# Cell_Balancing.net
KiCad netlist of a schematic drawn in Altium Designer
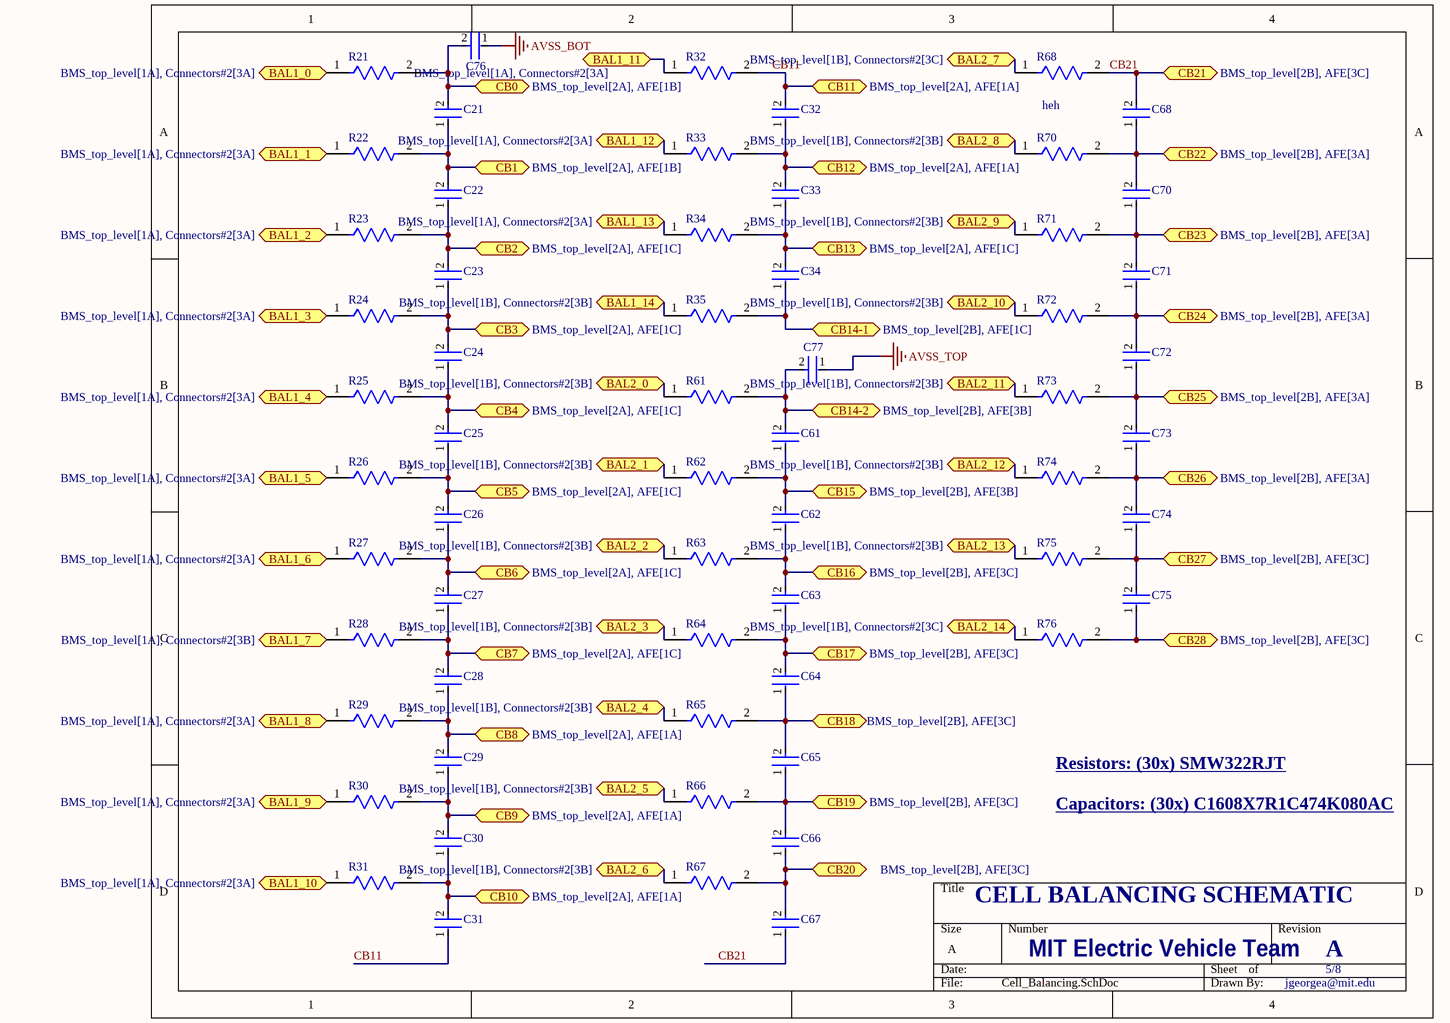
[diagram p0: Cell_Balancing.SchDoc]

(export (version "E")
  (design (tool "Eeschema 10.0.6"))
  (components
    (comp (ref "C21")
      (value "C1608X7R1C474K080AC")
      (footprint "FP-C1608-080-0_1-IPC_C")
      (description "Multilayer Ceramic Capacitors 470nF ±10% 16V X7R SMD 0603")
      (fields (field (name "VOLTAGE") "16V") (field (name "TOLERANCE") "10%"))
      (libsource (lib "Altium Content Vault") (part "236180d848d6139a670b325ea6854c9"))
    )
    (comp (ref "C22")
      (value "C1608X7R1C474K080AC")
      (footprint "FP-C1608-080-0_1-IPC_C")
      (description "Multilayer Ceramic Capacitors 470nF ±10% 16V X7R SMD 0603")
      (fields (field (name "VOLTAGE") "16V") (field (name "TOLERANCE") "10%"))
      (libsource (lib "Altium Content Vault") (part "236180d848d6139a670b325ea6854c9"))
    )
    (comp (ref "C23")
      (value "C1608X7R1C474K080AC")
      (footprint "FP-C1608-080-0_1-IPC_C")
      (description "Multilayer Ceramic Capacitors 470nF ±10% 16V X7R SMD 0603")
      (fields (field (name "VOLTAGE") "16V") (field (name "TOLERANCE") "10%"))
      (libsource (lib "Altium Content Vault") (part "236180d848d6139a670b325ea6854c9"))
    )
    (comp (ref "C24")
      (value "C1608X7R1C474K080AC")
      (footprint "FP-C1608-080-0_1-IPC_C")
      (description "Multilayer Ceramic Capacitors 470nF ±10% 16V X7R SMD 0603")
      (fields (field (name "VOLTAGE") "16V") (field (name "TOLERANCE") "10%"))
      (libsource (lib "Altium Content Vault") (part "236180d848d6139a670b325ea6854c9"))
    )
    (comp (ref "C25")
      (value "C1608X7R1C474K080AC")
      (footprint "FP-C1608-080-0_1-IPC_C")
      (description "Multilayer Ceramic Capacitors 470nF ±10% 16V X7R SMD 0603")
      (fields (field (name "VOLTAGE") "16V") (field (name "TOLERANCE") "10%"))
      (libsource (lib "Altium Content Vault") (part "236180d848d6139a670b325ea6854c9"))
    )
    (comp (ref "C26")
      (value "C1608X7R1C474K080AC")
      (footprint "FP-C1608-080-0_1-IPC_C")
      (description "Multilayer Ceramic Capacitors 470nF ±10% 16V X7R SMD 0603")
      (fields (field (name "VOLTAGE") "16V") (field (name "TOLERANCE") "10%"))
      (libsource (lib "Altium Content Vault") (part "236180d848d6139a670b325ea6854c9"))
    )
    (comp (ref "C27")
      (value "C1608X7R1C474K080AC")
      (footprint "FP-C1608-080-0_1-IPC_C")
      (description "Multilayer Ceramic Capacitors 470nF ±10% 16V X7R SMD 0603")
      (fields (field (name "VOLTAGE") "16V") (field (name "TOLERANCE") "10%"))
      (libsource (lib "Altium Content Vault") (part "236180d848d6139a670b325ea6854c9"))
    )
    (comp (ref "C28")
      (value "C1608X7R1C474K080AC")
      (footprint "FP-C1608-080-0_1-IPC_C")
      (description "Multilayer Ceramic Capacitors 470nF ±10% 16V X7R SMD 0603")
      (fields (field (name "VOLTAGE") "16V") (field (name "TOLERANCE") "10%"))
      (libsource (lib "Altium Content Vault") (part "236180d848d6139a670b325ea6854c9"))
    )
    (comp (ref "C29")
      (value "C1608X7R1C474K080AC")
      (footprint "FP-C1608-080-0_1-IPC_C")
      (description "Multilayer Ceramic Capacitors 470nF ±10% 16V X7R SMD 0603")
      (fields (field (name "VOLTAGE") "16V") (field (name "TOLERANCE") "10%"))
      (libsource (lib "Altium Content Vault") (part "236180d848d6139a670b325ea6854c9"))
    )
    (comp (ref "C30")
      (value "C1608X7R1C474K080AC")
      (footprint "FP-C1608-080-0_1-IPC_C")
      (description "Multilayer Ceramic Capacitors 470nF ±10% 16V X7R SMD 0603")
      (fields (field (name "VOLTAGE") "16V") (field (name "TOLERANCE") "10%"))
      (libsource (lib "Altium Content Vault") (part "236180d848d6139a670b325ea6854c9"))
    )
    (comp (ref "C31")
      (value "C1608X7R1C474K080AC")
      (footprint "FP-C1608-080-0_1-IPC_C")
      (description "Multilayer Ceramic Capacitors 470nF ±10% 16V X7R SMD 0603")
      (fields (field (name "VOLTAGE") "16V") (field (name "TOLERANCE") "10%"))
      (libsource (lib "Altium Content Vault") (part "236180d848d6139a670b325ea6854c9"))
    )
    (comp (ref "C32")
      (value "C1608X7R1C474K080AC")
      (footprint "FP-C1608-080-0_1-IPC_C")
      (description "Multilayer Ceramic Capacitors 470nF ±10% 16V X7R SMD 0603")
      (fields (field (name "VOLTAGE") "16V") (field (name "TOLERANCE") "10%"))
      (libsource (lib "Altium Content Vault") (part "236180d848d6139a670b325ea6854c9"))
    )
    (comp (ref "C33")
      (value "C1608X7R1C474K080AC")
      (footprint "FP-C1608-080-0_1-IPC_C")
      (description "Multilayer Ceramic Capacitors 470nF ±10% 16V X7R SMD 0603")
      (fields (field (name "VOLTAGE") "16V") (field (name "TOLERANCE") "10%"))
      (libsource (lib "Altium Content Vault") (part "236180d848d6139a670b325ea6854c9"))
    )
    (comp (ref "C34")
      (value "C1608X7R1C474K080AC")
      (footprint "FP-C1608-080-0_1-IPC_C")
      (description "Multilayer Ceramic Capacitors 470nF ±10% 16V X7R SMD 0603")
      (fields (field (name "VOLTAGE") "16V") (field (name "TOLERANCE") "10%"))
      (libsource (lib "Altium Content Vault") (part "236180d848d6139a670b325ea6854c9"))
    )
    (comp (ref "C61")
      (value "C1608X7R1C474K080AC")
      (footprint "FP-C1608-080-0_1-IPC_C")
      (description "Multilayer Ceramic Capacitors 470nF ±10% 16V X7R SMD 0603")
      (fields (field (name "VOLTAGE") "16V") (field (name "TOLERANCE") "10%"))
      (libsource (lib "Altium Content Vault") (part "236180d848d6139a670b325ea6854c9"))
    )
    (comp (ref "C62")
      (value "C1608X7R1C474K080AC")
      (footprint "FP-C1608-080-0_1-IPC_C")
      (description "Multilayer Ceramic Capacitors 470nF ±10% 16V X7R SMD 0603")
      (fields (field (name "VOLTAGE") "16V") (field (name "TOLERANCE") "10%"))
      (libsource (lib "Altium Content Vault") (part "236180d848d6139a670b325ea6854c9"))
    )
    (comp (ref "C63")
      (value "C1608X7R1C474K080AC")
      (footprint "FP-C1608-080-0_1-IPC_C")
      (description "Multilayer Ceramic Capacitors 470nF ±10% 16V X7R SMD 0603")
      (fields (field (name "VOLTAGE") "16V") (field (name "TOLERANCE") "10%"))
      (libsource (lib "Altium Content Vault") (part "236180d848d6139a670b325ea6854c9"))
    )
    (comp (ref "C64")
      (value "C1608X7R1C474K080AC")
      (footprint "FP-C1608-080-0_1-IPC_C")
      (description "Multilayer Ceramic Capacitors 470nF ±10% 16V X7R SMD 0603")
      (fields (field (name "VOLTAGE") "16V") (field (name "TOLERANCE") "10%"))
      (libsource (lib "Altium Content Vault") (part "236180d848d6139a670b325ea6854c9"))
    )
    (comp (ref "C65")
      (value "C1608X7R1C474K080AC")
      (footprint "FP-C1608-080-0_1-IPC_C")
      (description "Multilayer Ceramic Capacitors 470nF ±10% 16V X7R SMD 0603")
      (fields (field (name "VOLTAGE") "16V") (field (name "TOLERANCE") "10%"))
      (libsource (lib "Altium Content Vault") (part "236180d848d6139a670b325ea6854c9"))
    )
    (comp (ref "C66")
      (value "C1608X7R1C474K080AC")
      (footprint "FP-C1608-080-0_1-IPC_C")
      (description "Multilayer Ceramic Capacitors 470nF ±10% 16V X7R SMD 0603")
      (fields (field (name "VOLTAGE") "16V") (field (name "TOLERANCE") "10%"))
      (libsource (lib "Altium Content Vault") (part "236180d848d6139a670b325ea6854c9"))
    )
    (comp (ref "C67")
      (value "C1608X7R1C474K080AC")
      (footprint "FP-C1608-080-0_1-IPC_C")
      (description "Multilayer Ceramic Capacitors 470nF ±10% 16V X7R SMD 0603")
      (fields (field (name "VOLTAGE") "16V") (field (name "TOLERANCE") "10%"))
      (libsource (lib "Altium Content Vault") (part "236180d848d6139a670b325ea6854c9"))
    )
    (comp (ref "C68")
      (value "C1608X7R1C474K080AC")
      (footprint "FP-C1608-080-0_1-IPC_C")
      (description "Multilayer Ceramic Capacitors 470nF ±10% 16V X7R SMD 0603")
      (fields (field (name "VOLTAGE") "16V") (field (name "TOLERANCE") "10%"))
      (libsource (lib "Altium Content Vault") (part "236180d848d6139a670b325ea6854c9"))
    )
    (comp (ref "C70")
      (value "C1608X7R1C474K080AC")
      (footprint "FP-C1608-080-0_1-IPC_C")
      (description "Multilayer Ceramic Capacitors 470nF ±10% 16V X7R SMD 0603")
      (fields (field (name "VOLTAGE") "16V") (field (name "TOLERANCE") "10%"))
      (libsource (lib "Altium Content Vault") (part "236180d848d6139a670b325ea6854c9"))
    )
    (comp (ref "C71")
      (value "C1608X7R1C474K080AC")
      (footprint "FP-C1608-080-0_1-IPC_C")
      (description "Multilayer Ceramic Capacitors 470nF ±10% 16V X7R SMD 0603")
      (fields (field (name "VOLTAGE") "16V") (field (name "TOLERANCE") "10%"))
      (libsource (lib "Altium Content Vault") (part "236180d848d6139a670b325ea6854c9"))
    )
    (comp (ref "C72")
      (value "C1608X7R1C474K080AC")
      (footprint "FP-C1608-080-0_1-IPC_C")
      (description "Multilayer Ceramic Capacitors 470nF ±10% 16V X7R SMD 0603")
      (fields (field (name "VOLTAGE") "16V") (field (name "TOLERANCE") "10%"))
      (libsource (lib "Altium Content Vault") (part "236180d848d6139a670b325ea6854c9"))
    )
    (comp (ref "C73")
      (value "C1608X7R1C474K080AC")
      (footprint "FP-C1608-080-0_1-IPC_C")
      (description "Multilayer Ceramic Capacitors 470nF ±10% 16V X7R SMD 0603")
      (fields (field (name "VOLTAGE") "16V") (field (name "TOLERANCE") "10%"))
      (libsource (lib "Altium Content Vault") (part "236180d848d6139a670b325ea6854c9"))
    )
    (comp (ref "C74")
      (value "C1608X7R1C474K080AC")
      (footprint "FP-C1608-080-0_1-IPC_C")
      (description "Multilayer Ceramic Capacitors 470nF ±10% 16V X7R SMD 0603")
      (fields (field (name "VOLTAGE") "16V") (field (name "TOLERANCE") "10%"))
      (libsource (lib "Altium Content Vault") (part "236180d848d6139a670b325ea6854c9"))
    )
    (comp (ref "C75")
      (value "C1608X7R1C474K080AC")
      (footprint "FP-C1608-080-0_1-IPC_C")
      (description "Multilayer Ceramic Capacitors 470nF ±10% 16V X7R SMD 0603")
      (fields (field (name "VOLTAGE") "16V") (field (name "TOLERANCE") "10%"))
      (libsource (lib "Altium Content Vault") (part "236180d848d6139a670b325ea6854c9"))
    )
    (comp (ref "C76")
      (value "C1608X7R1C474K080AC")
      (footprint "FP-C1608-080-0_1-IPC_C")
      (description "Multilayer Ceramic Capacitors 470nF ±10% 16V X7R SMD 0603")
      (fields (field (name "VOLTAGE") "16V") (field (name "TOLERANCE") "10%"))
      (libsource (lib "Altium Content Vault") (part "236180d848d6139a670b325ea6854c9"))
    )
    (comp (ref "C77")
      (value "C1608X7R1C474K080AC")
      (footprint "FP-C1608-080-0_1-IPC_C")
      (description "Multilayer Ceramic Capacitors 470nF ±10% 16V X7R SMD 0603")
      (fields (field (name "VOLTAGE") "16V") (field (name "TOLERANCE") "10%"))
      (libsource (lib "Altium Content Vault") (part "236180d848d6139a670b325ea6854c9"))
    )
    (comp (ref "R21")
      (value "SMW322RJT")
      (footprint "FP-SM_3-MFG")
      (description "RES SMD 22 OHM 5% 3W 4122")
      (fields
        (field (name "TOLERANCE") "5%")
        (field (name "OCTOPART") "https://octopart.com/smw322rjt-te+connectivity-40971089")
      )
      (libsource (lib "Altium Content Vault") (part "1029c3af85768c4190bb7ad29bc67b5"))
    )
    (comp (ref "R22")
      (value "SMW322RJT")
      (footprint "FP-SM_3-MFG")
      (description "RES SMD 22 OHM 5% 3W 4122")
      (fields
        (field (name "TOLERANCE") "5%")
        (field (name "OCTOPART") "https://octopart.com/smw322rjt-te+connectivity-40971089")
      )
      (libsource (lib "Altium Content Vault") (part "1029c3af85768c4190bb7ad29bc67b5"))
    )
    (comp (ref "R23")
      (value "SMW322RJT")
      (footprint "FP-SM_3-MFG")
      (description "RES SMD 22 OHM 5% 3W 4122")
      (fields
        (field (name "TOLERANCE") "5%")
        (field (name "OCTOPART") "https://octopart.com/smw322rjt-te+connectivity-40971089")
      )
      (libsource (lib "Altium Content Vault") (part "1029c3af85768c4190bb7ad29bc67b5"))
    )
    (comp (ref "R24")
      (value "SMW322RJT")
      (footprint "FP-SM_3-MFG")
      (description "RES SMD 22 OHM 5% 3W 4122")
      (fields
        (field (name "TOLERANCE") "5%")
        (field (name "OCTOPART") "https://octopart.com/smw322rjt-te+connectivity-40971089")
      )
      (libsource (lib "Altium Content Vault") (part "1029c3af85768c4190bb7ad29bc67b5"))
    )
    (comp (ref "R25")
      (value "SMW322RJT")
      (footprint "FP-SM_3-MFG")
      (description "RES SMD 22 OHM 5% 3W 4122")
      (fields
        (field (name "TOLERANCE") "5%")
        (field (name "OCTOPART") "https://octopart.com/smw322rjt-te+connectivity-40971089")
      )
      (libsource (lib "Altium Content Vault") (part "1029c3af85768c4190bb7ad29bc67b5"))
    )
    (comp (ref "R26")
      (value "SMW322RJT")
      (footprint "FP-SM_3-MFG")
      (description "RES SMD 22 OHM 5% 3W 4122")
      (fields
        (field (name "TOLERANCE") "5%")
        (field (name "OCTOPART") "https://octopart.com/smw322rjt-te+connectivity-40971089")
      )
      (libsource (lib "Altium Content Vault") (part "1029c3af85768c4190bb7ad29bc67b5"))
    )
    (comp (ref "R27")
      (value "SMW322RJT")
      (footprint "FP-SM_3-MFG")
      (description "RES SMD 22 OHM 5% 3W 4122")
      (fields
        (field (name "TOLERANCE") "5%")
        (field (name "OCTOPART") "https://octopart.com/smw322rjt-te+connectivity-40971089")
      )
      (libsource (lib "Altium Content Vault") (part "1029c3af85768c4190bb7ad29bc67b5"))
    )
    (comp (ref "R28")
      (value "SMW322RJT")
      (footprint "FP-SM_3-MFG")
      (description "RES SMD 22 OHM 5% 3W 4122")
      (fields
        (field (name "TOLERANCE") "5%")
        (field (name "OCTOPART") "https://octopart.com/smw322rjt-te+connectivity-40971089")
      )
      (libsource (lib "Altium Content Vault") (part "1029c3af85768c4190bb7ad29bc67b5"))
    )
    (comp (ref "R29")
      (value "SMW322RJT")
      (footprint "FP-SM_3-MFG")
      (description "RES SMD 22 OHM 5% 3W 4122")
      (fields
        (field (name "TOLERANCE") "5%")
        (field (name "OCTOPART") "https://octopart.com/smw322rjt-te+connectivity-40971089")
      )
      (libsource (lib "Altium Content Vault") (part "1029c3af85768c4190bb7ad29bc67b5"))
    )
    (comp (ref "R30")
      (value "SMW322RJT")
      (footprint "FP-SM_3-MFG")
      (description "RES SMD 22 OHM 5% 3W 4122")
      (fields
        (field (name "TOLERANCE") "5%")
        (field (name "OCTOPART") "https://octopart.com/smw322rjt-te+connectivity-40971089")
      )
      (libsource (lib "Altium Content Vault") (part "1029c3af85768c4190bb7ad29bc67b5"))
    )
    (comp (ref "R31")
      (value "SMW322RJT")
      (footprint "FP-SM_3-MFG")
      (description "RES SMD 22 OHM 5% 3W 4122")
      (fields
        (field (name "TOLERANCE") "5%")
        (field (name "OCTOPART") "https://octopart.com/smw322rjt-te+connectivity-40971089")
      )
      (libsource (lib "Altium Content Vault") (part "1029c3af85768c4190bb7ad29bc67b5"))
    )
    (comp (ref "R32")
      (value "SMW322RJT")
      (footprint "FP-SM_3-MFG")
      (description "RES SMD 22 OHM 5% 3W 4122")
      (fields
        (field (name "TOLERANCE") "5%")
        (field (name "OCTOPART") "https://octopart.com/smw322rjt-te+connectivity-40971089")
      )
      (libsource (lib "Altium Content Vault") (part "1029c3af85768c4190bb7ad29bc67b5"))
    )
    (comp (ref "R33")
      (value "SMW322RJT")
      (footprint "FP-SM_3-MFG")
      (description "RES SMD 22 OHM 5% 3W 4122")
      (fields
        (field (name "TOLERANCE") "5%")
        (field (name "OCTOPART") "https://octopart.com/smw322rjt-te+connectivity-40971089")
      )
      (libsource (lib "Altium Content Vault") (part "1029c3af85768c4190bb7ad29bc67b5"))
    )
    (comp (ref "R34")
      (value "SMW322RJT")
      (footprint "FP-SM_3-MFG")
      (description "RES SMD 22 OHM 5% 3W 4122")
      (fields
        (field (name "TOLERANCE") "5%")
        (field (name "OCTOPART") "https://octopart.com/smw322rjt-te+connectivity-40971089")
      )
      (libsource (lib "Altium Content Vault") (part "1029c3af85768c4190bb7ad29bc67b5"))
    )
    (comp (ref "R35")
      (value "SMW322RJT")
      (footprint "FP-SM_3-MFG")
      (description "RES SMD 22 OHM 5% 3W 4122")
      (fields
        (field (name "TOLERANCE") "5%")
        (field (name "OCTOPART") "https://octopart.com/smw322rjt-te+connectivity-40971089")
      )
      (libsource (lib "Altium Content Vault") (part "1029c3af85768c4190bb7ad29bc67b5"))
    )
    (comp (ref "R61")
      (value "SMW322RJT")
      (footprint "FP-SM_3-MFG")
      (description "RES SMD 22 OHM 5% 3W 4122")
      (fields
        (field (name "TOLERANCE") "5%")
        (field (name "OCTOPART") "https://octopart.com/smw322rjt-te+connectivity-40971089")
      )
      (libsource (lib "Altium Content Vault") (part "1029c3af85768c4190bb7ad29bc67b5"))
    )
    (comp (ref "R62")
      (value "SMW322RJT")
      (footprint "FP-SM_3-MFG")
      (description "RES SMD 22 OHM 5% 3W 4122")
      (fields
        (field (name "TOLERANCE") "5%")
        (field (name "OCTOPART") "https://octopart.com/smw322rjt-te+connectivity-40971089")
      )
      (libsource (lib "Altium Content Vault") (part "1029c3af85768c4190bb7ad29bc67b5"))
    )
    (comp (ref "R63")
      (value "SMW322RJT")
      (footprint "FP-SM_3-MFG")
      (description "RES SMD 22 OHM 5% 3W 4122")
      (fields
        (field (name "TOLERANCE") "5%")
        (field (name "OCTOPART") "https://octopart.com/smw322rjt-te+connectivity-40971089")
      )
      (libsource (lib "Altium Content Vault") (part "1029c3af85768c4190bb7ad29bc67b5"))
    )
    (comp (ref "R64")
      (value "SMW322RJT")
      (footprint "FP-SM_3-MFG")
      (description "RES SMD 22 OHM 5% 3W 4122")
      (fields
        (field (name "TOLERANCE") "5%")
        (field (name "OCTOPART") "https://octopart.com/smw322rjt-te+connectivity-40971089")
      )
      (libsource (lib "Altium Content Vault") (part "1029c3af85768c4190bb7ad29bc67b5"))
    )
    (comp (ref "R65")
      (value "SMW322RJT")
      (footprint "FP-SM_3-MFG")
      (description "RES SMD 22 OHM 5% 3W 4122")
      (fields
        (field (name "TOLERANCE") "5%")
        (field (name "OCTOPART") "https://octopart.com/smw322rjt-te+connectivity-40971089")
      )
      (libsource (lib "Altium Content Vault") (part "1029c3af85768c4190bb7ad29bc67b5"))
    )
    (comp (ref "R66")
      (value "SMW322RJT")
      (footprint "FP-SM_3-MFG")
      (description "RES SMD 22 OHM 5% 3W 4122")
      (fields
        (field (name "TOLERANCE") "5%")
        (field (name "OCTOPART") "https://octopart.com/smw322rjt-te+connectivity-40971089")
      )
      (libsource (lib "Altium Content Vault") (part "1029c3af85768c4190bb7ad29bc67b5"))
    )
    (comp (ref "R67")
      (value "SMW322RJT")
      (footprint "FP-SM_3-MFG")
      (description "RES SMD 22 OHM 5% 3W 4122")
      (fields
        (field (name "TOLERANCE") "5%")
        (field (name "OCTOPART") "https://octopart.com/smw322rjt-te+connectivity-40971089")
      )
      (libsource (lib "Altium Content Vault") (part "1029c3af85768c4190bb7ad29bc67b5"))
    )
    (comp (ref "R68")
      (value "SMW322RJT")
      (footprint "FP-SM_3-MFG")
      (description "RES SMD 22 OHM 5% 3W 4122")
      (fields
        (field (name "TOLERANCE") "5%")
        (field (name "OCTOPART") "https://octopart.com/smw322rjt-te+connectivity-40971089")
      )
      (libsource (lib "Altium Content Vault") (part "1029c3af85768c4190bb7ad29bc67b5"))
    )
    (comp (ref "R70")
      (value "SMW322RJT")
      (footprint "FP-SM_3-MFG")
      (description "RES SMD 22 OHM 5% 3W 4122")
      (fields
        (field (name "TOLERANCE") "5%")
        (field (name "OCTOPART") "https://octopart.com/smw322rjt-te+connectivity-40971089")
      )
      (libsource (lib "Altium Content Vault") (part "1029c3af85768c4190bb7ad29bc67b5"))
    )
    (comp (ref "R71")
      (value "SMW322RJT")
      (footprint "FP-SM_3-MFG")
      (description "RES SMD 22 OHM 5% 3W 4122")
      (fields
        (field (name "TOLERANCE") "5%")
        (field (name "OCTOPART") "https://octopart.com/smw322rjt-te+connectivity-40971089")
      )
      (libsource (lib "Altium Content Vault") (part "1029c3af85768c4190bb7ad29bc67b5"))
    )
    (comp (ref "R72")
      (value "SMW322RJT")
      (footprint "FP-SM_3-MFG")
      (description "RES SMD 22 OHM 5% 3W 4122")
      (fields
        (field (name "TOLERANCE") "5%")
        (field (name "OCTOPART") "https://octopart.com/smw322rjt-te+connectivity-40971089")
      )
      (libsource (lib "Altium Content Vault") (part "1029c3af85768c4190bb7ad29bc67b5"))
    )
    (comp (ref "R73")
      (value "SMW322RJT")
      (footprint "FP-SM_3-MFG")
      (description "RES SMD 22 OHM 5% 3W 4122")
      (fields
        (field (name "TOLERANCE") "5%")
        (field (name "OCTOPART") "https://octopart.com/smw322rjt-te+connectivity-40971089")
      )
      (libsource (lib "Altium Content Vault") (part "1029c3af85768c4190bb7ad29bc67b5"))
    )
    (comp (ref "R74")
      (value "SMW322RJT")
      (footprint "FP-SM_3-MFG")
      (description "RES SMD 22 OHM 5% 3W 4122")
      (fields
        (field (name "TOLERANCE") "5%")
        (field (name "OCTOPART") "https://octopart.com/smw322rjt-te+connectivity-40971089")
      )
      (libsource (lib "Altium Content Vault") (part "1029c3af85768c4190bb7ad29bc67b5"))
    )
    (comp (ref "R75")
      (value "SMW322RJT")
      (footprint "FP-SM_3-MFG")
      (description "RES SMD 22 OHM 5% 3W 4122")
      (fields
        (field (name "TOLERANCE") "5%")
        (field (name "OCTOPART") "https://octopart.com/smw322rjt-te+connectivity-40971089")
      )
      (libsource (lib "Altium Content Vault") (part "1029c3af85768c4190bb7ad29bc67b5"))
    )
    (comp (ref "R76")
      (value "SMW322RJT")
      (footprint "FP-SM_3-MFG")
      (description "RES SMD 22 OHM 5% 3W 4122")
      (fields
        (field (name "TOLERANCE") "5%")
        (field (name "OCTOPART") "https://octopart.com/smw322rjt-te+connectivity-40971089")
      )
      (libsource (lib "Altium Content Vault") (part "1029c3af85768c4190bb7ad29bc67b5"))
    )
  )
  (nets
    (net (code "1") (name "/BAL1_0") (class "Default")
      (node (ref "R21") (pin "1") (pinfunction "1_1") (pintype "passive"))
    )
    (net (code "2") (name "/BAL1_1") (class "Default")
      (node (ref "R22") (pin "1") (pinfunction "1_1") (pintype "passive"))
    )
    (net (code "3") (name "/BAL1_2") (class "Default")
      (node (ref "R23") (pin "1") (pinfunction "1_1") (pintype "passive"))
    )
    (net (code "4") (name "/BAL1_3") (class "Default")
      (node (ref "R24") (pin "1") (pinfunction "1_1") (pintype "passive"))
    )
    (net (code "5") (name "/BAL1_4") (class "Default")
      (node (ref "R25") (pin "1") (pinfunction "1_1") (pintype "passive"))
    )
    (net (code "6") (name "/BAL1_5") (class "Default")
      (node (ref "R26") (pin "1") (pinfunction "1_1") (pintype "passive"))
    )
    (net (code "7") (name "/BAL1_6") (class "Default")
      (node (ref "R27") (pin "1") (pinfunction "1_1") (pintype "passive"))
    )
    (net (code "8") (name "/BAL1_7") (class "Default")
      (node (ref "R28") (pin "1") (pinfunction "1_1") (pintype "passive"))
    )
    (net (code "9") (name "/BAL1_8") (class "Default")
      (node (ref "R29") (pin "1") (pinfunction "1_1") (pintype "passive"))
    )
    (net (code "10") (name "/BAL1_9") (class "Default")
      (node (ref "R30") (pin "1") (pinfunction "1_1") (pintype "passive"))
    )
    (net (code "11") (name "/BAL1_10") (class "Default")
      (node (ref "R31") (pin "1") (pinfunction "1_1") (pintype "passive"))
    )
    (net (code "12") (name "/BAL1_11") (class "Default")
      (node (ref "R32") (pin "1") (pinfunction "1_1") (pintype "passive"))
    )
    (net (code "13") (name "/BAL1_12") (class "Default")
      (node (ref "R33") (pin "1") (pinfunction "1_1") (pintype "passive"))
    )
    (net (code "14") (name "/BAL1_13") (class "Default")
      (node (ref "R34") (pin "1") (pinfunction "1_1") (pintype "passive"))
    )
    (net (code "15") (name "/BAL1_14") (class "Default")
      (node (ref "R35") (pin "1") (pinfunction "1_1") (pintype "passive"))
    )
    (net (code "16") (name "/BAL2_0") (class "Default")
      (node (ref "R61") (pin "1") (pinfunction "1_1") (pintype "passive"))
    )
    (net (code "17") (name "/BAL2_1") (class "Default")
      (node (ref "R62") (pin "1") (pinfunction "1_1") (pintype "passive"))
    )
    (net (code "18") (name "/BAL2_2") (class "Default")
      (node (ref "R63") (pin "1") (pinfunction "1_1") (pintype "passive"))
    )
    (net (code "19") (name "/BAL2_3") (class "Default")
      (node (ref "R64") (pin "1") (pinfunction "1_1") (pintype "passive"))
    )
    (net (code "20") (name "/BAL2_4") (class "Default")
      (node (ref "R65") (pin "1") (pinfunction "1_1") (pintype "passive"))
    )
    (net (code "21") (name "/BAL2_5") (class "Default")
      (node (ref "R66") (pin "1") (pinfunction "1_1") (pintype "passive"))
    )
    (net (code "22") (name "/BAL2_6") (class "Default")
      (node (ref "R67") (pin "1") (pinfunction "1_1") (pintype "passive"))
    )
    (net (code "23") (name "/BAL2_7") (class "Default")
      (node (ref "R68") (pin "1") (pinfunction "1_1") (pintype "passive"))
    )
    (net (code "24") (name "/BAL2_8") (class "Default")
      (node (ref "R70") (pin "1") (pinfunction "1_1") (pintype "passive"))
    )
    (net (code "25") (name "/BAL2_9") (class "Default")
      (node (ref "R71") (pin "1") (pinfunction "1_1") (pintype "passive"))
    )
    (net (code "26") (name "/BAL2_10") (class "Default")
      (node (ref "R72") (pin "1") (pinfunction "1_1") (pintype "passive"))
    )
    (net (code "27") (name "/BAL2_11") (class "Default")
      (node (ref "R73") (pin "1") (pinfunction "1_1") (pintype "passive"))
    )
    (net (code "28") (name "/BAL2_12") (class "Default")
      (node (ref "R74") (pin "1") (pinfunction "1_1") (pintype "passive"))
    )
    (net (code "29") (name "/BAL2_13") (class "Default")
      (node (ref "R75") (pin "1") (pinfunction "1_1") (pintype "passive"))
    )
    (net (code "30") (name "/BAL2_14") (class "Default")
      (node (ref "R76") (pin "1") (pinfunction "1_1") (pintype "passive"))
    )
    (net (code "31") (name "/CB0") (class "Default")
      (node (ref "C21") (pin "2") (pinfunction "2_2") (pintype "passive"))
      (node (ref "C76") (pin "2") (pinfunction "2_2") (pintype "passive"))
      (node (ref "R21") (pin "2") (pinfunction "2_2") (pintype "passive"))
    )
    (net (code "32") (name "/CB1") (class "Default")
      (node (ref "C21") (pin "1") (pinfunction "1_1") (pintype "passive"))
      (node (ref "C22") (pin "2") (pinfunction "2_2") (pintype "passive"))
      (node (ref "R22") (pin "2") (pinfunction "2_2") (pintype "passive"))
    )
    (net (code "33") (name "/CB2") (class "Default")
      (node (ref "C22") (pin "1") (pinfunction "1_1") (pintype "passive"))
      (node (ref "C23") (pin "2") (pinfunction "2_2") (pintype "passive"))
      (node (ref "R23") (pin "2") (pinfunction "2_2") (pintype "passive"))
    )
    (net (code "34") (name "/CB3") (class "Default")
      (node (ref "C23") (pin "1") (pinfunction "1_1") (pintype "passive"))
      (node (ref "C24") (pin "2") (pinfunction "2_2") (pintype "passive"))
      (node (ref "R24") (pin "2") (pinfunction "2_2") (pintype "passive"))
    )
    (net (code "35") (name "/CB4") (class "Default")
      (node (ref "C24") (pin "1") (pinfunction "1_1") (pintype "passive"))
      (node (ref "C25") (pin "2") (pinfunction "2_2") (pintype "passive"))
      (node (ref "R25") (pin "2") (pinfunction "2_2") (pintype "passive"))
    )
    (net (code "36") (name "/CB5") (class "Default")
      (node (ref "C25") (pin "1") (pinfunction "1_1") (pintype "passive"))
      (node (ref "C26") (pin "2") (pinfunction "2_2") (pintype "passive"))
      (node (ref "R26") (pin "2") (pinfunction "2_2") (pintype "passive"))
    )
    (net (code "37") (name "/CB6") (class "Default")
      (node (ref "C26") (pin "1") (pinfunction "1_1") (pintype "passive"))
      (node (ref "C27") (pin "2") (pinfunction "2_2") (pintype "passive"))
      (node (ref "R27") (pin "2") (pinfunction "2_2") (pintype "passive"))
    )
    (net (code "38") (name "/CB7") (class "Default")
      (node (ref "C27") (pin "1") (pinfunction "1_1") (pintype "passive"))
      (node (ref "C28") (pin "2") (pinfunction "2_2") (pintype "passive"))
      (node (ref "R28") (pin "2") (pinfunction "2_2") (pintype "passive"))
    )
    (net (code "39") (name "/CB8") (class "Default")
      (node (ref "C28") (pin "1") (pinfunction "1_1") (pintype "passive"))
      (node (ref "C29") (pin "2") (pinfunction "2_2") (pintype "passive"))
      (node (ref "R29") (pin "2") (pinfunction "2_2") (pintype "passive"))
    )
    (net (code "40") (name "/CB9") (class "Default")
      (node (ref "C29") (pin "1") (pinfunction "1_1") (pintype "passive"))
      (node (ref "C30") (pin "2") (pinfunction "2_2") (pintype "passive"))
      (node (ref "R30") (pin "2") (pinfunction "2_2") (pintype "passive"))
    )
    (net (code "41") (name "/CB10") (class "Default")
      (node (ref "C30") (pin "1") (pinfunction "1_1") (pintype "passive"))
      (node (ref "C31") (pin "2") (pinfunction "2_2") (pintype "passive"))
      (node (ref "R31") (pin "2") (pinfunction "2_2") (pintype "passive"))
    )
    (net (code "42") (name "/CB11") (class "Default")
      (node (ref "C31") (pin "1") (pinfunction "1_1") (pintype "passive"))
      (node (ref "C32") (pin "2") (pinfunction "2_2") (pintype "passive"))
      (node (ref "R32") (pin "2") (pinfunction "2_2") (pintype "passive"))
    )
    (net (code "43") (name "/CB12") (class "Default")
      (node (ref "C32") (pin "1") (pinfunction "1_1") (pintype "passive"))
      (node (ref "C33") (pin "2") (pinfunction "2_2") (pintype "passive"))
      (node (ref "R33") (pin "2") (pinfunction "2_2") (pintype "passive"))
    )
    (net (code "44") (name "/CB13") (class "Default")
      (node (ref "C33") (pin "1") (pinfunction "1_1") (pintype "passive"))
      (node (ref "C34") (pin "2") (pinfunction "2_2") (pintype "passive"))
      (node (ref "R34") (pin "2") (pinfunction "2_2") (pintype "passive"))
    )
    (net (code "45") (name "/CB14-1") (class "Default")
      (node (ref "C34") (pin "1") (pinfunction "1_1") (pintype "passive"))
      (node (ref "R35") (pin "2") (pinfunction "2_2") (pintype "passive"))
    )
    (net (code "46") (name "/CB14-2") (class "Default")
      (node (ref "C61") (pin "2") (pinfunction "2_2") (pintype "passive"))
      (node (ref "C77") (pin "2") (pinfunction "2_2") (pintype "passive"))
      (node (ref "R61") (pin "2") (pinfunction "2_2") (pintype "passive"))
    )
    (net (code "47") (name "/CB15") (class "Default")
      (node (ref "C61") (pin "1") (pinfunction "1_1") (pintype "passive"))
      (node (ref "C62") (pin "2") (pinfunction "2_2") (pintype "passive"))
      (node (ref "R62") (pin "2") (pinfunction "2_2") (pintype "passive"))
    )
    (net (code "48") (name "/CB16") (class "Default")
      (node (ref "C62") (pin "1") (pinfunction "1_1") (pintype "passive"))
      (node (ref "C63") (pin "2") (pinfunction "2_2") (pintype "passive"))
      (node (ref "R63") (pin "2") (pinfunction "2_2") (pintype "passive"))
    )
    (net (code "49") (name "/CB17") (class "Default")
      (node (ref "C63") (pin "1") (pinfunction "1_1") (pintype "passive"))
      (node (ref "C64") (pin "2") (pinfunction "2_2") (pintype "passive"))
      (node (ref "R64") (pin "2") (pinfunction "2_2") (pintype "passive"))
    )
    (net (code "50") (name "/CB18") (class "Default")
      (node (ref "C64") (pin "1") (pinfunction "1_1") (pintype "passive"))
      (node (ref "C65") (pin "2") (pinfunction "2_2") (pintype "passive"))
      (node (ref "R65") (pin "2") (pinfunction "2_2") (pintype "passive"))
    )
    (net (code "51") (name "/CB19") (class "Default")
      (node (ref "C65") (pin "1") (pinfunction "1_1") (pintype "passive"))
      (node (ref "C66") (pin "2") (pinfunction "2_2") (pintype "passive"))
      (node (ref "R66") (pin "2") (pinfunction "2_2") (pintype "passive"))
    )
    (net (code "52") (name "/CB20") (class "Default")
      (node (ref "C66") (pin "1") (pinfunction "1_1") (pintype "passive"))
      (node (ref "C67") (pin "2") (pinfunction "2_2") (pintype "passive"))
      (node (ref "R67") (pin "2") (pinfunction "2_2") (pintype "passive"))
    )
    (net (code "53") (name "/CB21") (class "Default")
      (node (ref "C67") (pin "1") (pinfunction "1_1") (pintype "passive"))
      (node (ref "C68") (pin "2") (pinfunction "2_2") (pintype "passive"))
      (node (ref "R68") (pin "2") (pinfunction "2_2") (pintype "passive"))
    )
    (net (code "54") (name "/CB22") (class "Default")
      (node (ref "C68") (pin "1") (pinfunction "1_1") (pintype "passive"))
      (node (ref "C70") (pin "2") (pinfunction "2_2") (pintype "passive"))
      (node (ref "R70") (pin "2") (pinfunction "2_2") (pintype "passive"))
    )
    (net (code "55") (name "/CB23") (class "Default")
      (node (ref "C70") (pin "1") (pinfunction "1_1") (pintype "passive"))
      (node (ref "C71") (pin "2") (pinfunction "2_2") (pintype "passive"))
      (node (ref "R71") (pin "2") (pinfunction "2_2") (pintype "passive"))
    )
    (net (code "56") (name "/CB24") (class "Default")
      (node (ref "C71") (pin "1") (pinfunction "1_1") (pintype "passive"))
      (node (ref "C72") (pin "2") (pinfunction "2_2") (pintype "passive"))
      (node (ref "R72") (pin "2") (pinfunction "2_2") (pintype "passive"))
    )
    (net (code "57") (name "/CB25") (class "Default")
      (node (ref "C72") (pin "1") (pinfunction "1_1") (pintype "passive"))
      (node (ref "C73") (pin "2") (pinfunction "2_2") (pintype "passive"))
      (node (ref "R73") (pin "2") (pinfunction "2_2") (pintype "passive"))
    )
    (net (code "58") (name "/CB26") (class "Default")
      (node (ref "C73") (pin "1") (pinfunction "1_1") (pintype "passive"))
      (node (ref "C74") (pin "2") (pinfunction "2_2") (pintype "passive"))
      (node (ref "R74") (pin "2") (pinfunction "2_2") (pintype "passive"))
    )
    (net (code "59") (name "/CB27") (class "Default")
      (node (ref "C74") (pin "1") (pinfunction "1_1") (pintype "passive"))
      (node (ref "C75") (pin "2") (pinfunction "2_2") (pintype "passive"))
      (node (ref "R75") (pin "2") (pinfunction "2_2") (pintype "passive"))
    )
    (net (code "60") (name "/CB28") (class "Default")
      (node (ref "C75") (pin "1") (pinfunction "1_1") (pintype "passive"))
      (node (ref "R76") (pin "2") (pinfunction "2_2") (pintype "passive"))
    )
    (net (code "61") (name "AVSS_BOT") (class "Default")
      (node (ref "C76") (pin "1") (pinfunction "1_1") (pintype "passive"))
    )
    (net (code "62") (name "AVSS_TOP") (class "Default")
      (node (ref "C77") (pin "1") (pinfunction "1_1") (pintype "passive"))
    )
  )
)
